# Druga_p_ytka.net
KiCad netlist of a schematic drawn in EAGLE
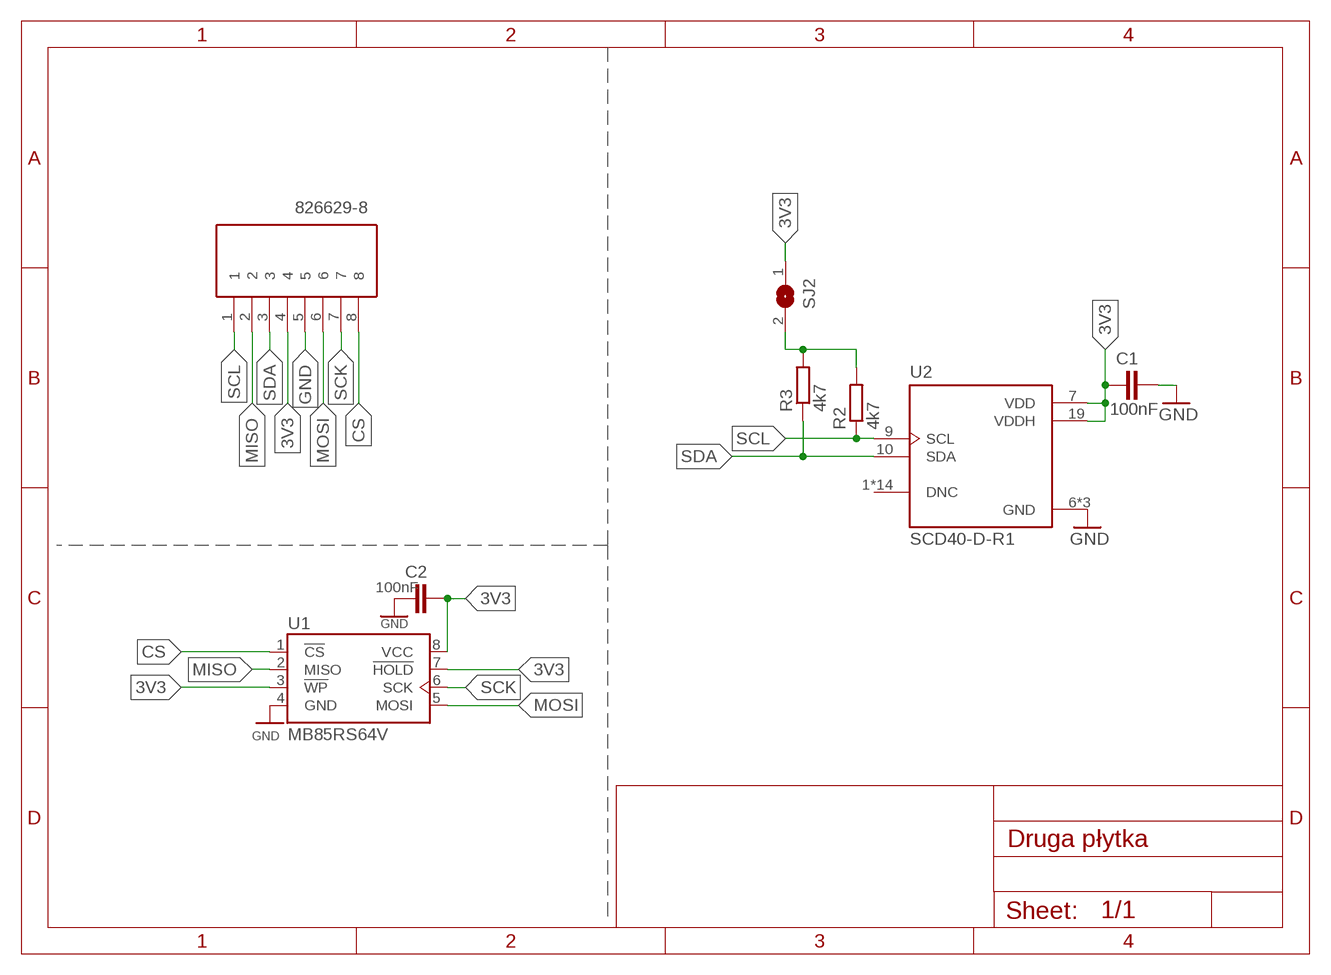
[diagram p0: schematic, sheet 1]

(export (version "E")
  (design (tool "Eeschema 10.0.6"))
  (components
    (comp (ref "C1")
      (value "100nF")
      (footprint "eagle-import:C0402")
      (libsource (lib "eagle-import") (part "C-EUC0402"))
    )
    (comp (ref "C2")
      (value "100nF")
      (footprint "eagle-import:C0402")
      (libsource (lib "eagle-import") (part "C-EUC0402"))
    )
    (comp (ref "J1")
      (value "826629-8")
      (footprint "eagle-import:HDRV8W63P0X254_1X8_2032X250X95")
      (fields (field (name "MOUSER_PART_NUMBER") "571-826629-8"))
      (libsource (lib "eagle-import") (part "826629-8"))
    )
    (comp (ref "R2")
      (value "4k7")
      (footprint "eagle-import:R1206")
      (libsource (lib "eagle-import") (part "R-EU_R1206"))
    )
    (comp (ref "R3")
      (value "4k7")
      (footprint "eagle-import:R1206")
      (libsource (lib "eagle-import") (part "R-EU_R1206"))
    )
    (comp (ref "SJ2") (value "SJ") (footprint "eagle-import:SJ") (libsource (lib "eagle-import") (part "SJ")))
    (comp (ref "U1")
      (value "MB85RS64V")
      (footprint "eagle-import:SOIC127P600X155-8_R159_68_374R15")
      (fields (field (name "MF") "Fujitsu"))
      (libsource (lib "eagle-import") (part "MB85RS64V"))
    )
    (comp (ref "U2")
      (value "SCD40-D-R1")
      (footprint "eagle-import:XDCR_SCD40-D-R1")
      (fields (field (name "MF") "Sensirion AG"))
      (libsource (lib "eagle-import") (part "SCD40-D-R1"))
    )
  )
  (nets
    (net (code "1") (name "3V3") (class "Default")
      (node (ref "C1") (pin "2") (pinfunction "2_2") (pintype "passive"))
      (node (ref "C2") (pin "1") (pinfunction "1_1") (pintype "passive"))
      (node (ref "J1") (pin "4") (pinfunction "4_4") (pintype "bidirectional"))
      (node (ref "SJ2") (pin "1") (pinfunction "1_1") (pintype "passive"))
      (node (ref "U1") (pin "3") (pinfunction "~{WP}_3") (pintype "input"))
      (node (ref "U1") (pin "7") (pinfunction "~{HOLD}_7") (pintype "input"))
      (node (ref "U1") (pin "8") (pinfunction "VCC_8") (pintype "power_in"))
      (node (ref "U2") (pin "19") (pinfunction "VDDH_19") (pintype "power_in"))
      (node (ref "U2") (pin "7") (pinfunction "VDD_7") (pintype "power_in"))
    )
    (net (code "2") (name "CS") (class "Default")
      (node (ref "J1") (pin "8") (pinfunction "8_8") (pintype "bidirectional"))
      (node (ref "U1") (pin "1") (pinfunction "~{CS}_1") (pintype "input"))
    )
    (net (code "3") (name "GND") (class "Default")
      (node (ref "C1") (pin "1") (pinfunction "1_1") (pintype "passive"))
      (node (ref "C2") (pin "2") (pinfunction "2_2") (pintype "passive"))
      (node (ref "J1") (pin "5") (pinfunction "5_5") (pintype "bidirectional"))
      (node (ref "U1") (pin "4") (pinfunction "GND_4") (pintype "power_in"))
      (node (ref "U2") (pin "20") (pinfunction "GND_20") (pintype "power_in"))
      (node (ref "U2") (pin "21") (pinfunction "GND_21") (pintype "power_in"))
      (node (ref "U2") (pin "6") (pinfunction "GND_6") (pintype "power_in"))
    )
    (net (code "4") (name "MISO") (class "Default")
      (node (ref "J1") (pin "2") (pinfunction "2_2") (pintype "bidirectional"))
      (node (ref "U1") (pin "2") (pinfunction "MISO_2") (pintype "output"))
    )
    (net (code "5") (name "MOSI") (class "Default")
      (node (ref "J1") (pin "6") (pinfunction "6_6") (pintype "bidirectional"))
      (node (ref "U1") (pin "5") (pinfunction "MOSI_5") (pintype "input"))
    )
    (net (code "6") (name "Net-(R2-Pad2)") (class "Default")
      (node (ref "R2") (pin "2") (pinfunction "2_2") (pintype "passive"))
      (node (ref "R3") (pin "2") (pinfunction "2_2") (pintype "passive"))
      (node (ref "SJ2") (pin "2") (pinfunction "2_2") (pintype "passive"))
    )
    (net (code "7") (name "SCK") (class "Default")
      (node (ref "J1") (pin "7") (pinfunction "7_7") (pintype "bidirectional"))
      (node (ref "U1") (pin "6") (pinfunction "SCK_6") (pintype "input"))
    )
    (net (code "8") (name "SCL") (class "Default")
      (node (ref "J1") (pin "1") (pinfunction "1_1") (pintype "bidirectional"))
      (node (ref "R2") (pin "1") (pinfunction "1_1") (pintype "passive"))
      (node (ref "U2") (pin "9") (pinfunction "SCL_9") (pintype "input"))
    )
    (net (code "9") (name "SDA") (class "Default")
      (node (ref "J1") (pin "3") (pinfunction "3_3") (pintype "bidirectional"))
      (node (ref "R3") (pin "1") (pinfunction "1_1") (pintype "passive"))
      (node (ref "U2") (pin "10") (pinfunction "SDA_10") (pintype "bidirectional"))
    )
    (net (code "10") (name "unconnected-(U2-DNC-Pad1)") (class "Default")
      (node (ref "U2") (pin "1") (pinfunction "DNC_1") (pintype "no_connect"))
    )
    (net (code "11") (name "unconnected-(U2-DNC-Pad2)") (class "Default")
      (node (ref "U2") (pin "2") (pinfunction "DNC_2") (pintype "no_connect"))
    )
    (net (code "12") (name "unconnected-(U2-DNC-Pad3)") (class "Default")
      (node (ref "U2") (pin "3") (pinfunction "DNC_3") (pintype "no_connect"))
    )
    (net (code "13") (name "unconnected-(U2-DNC-Pad4)") (class "Default")
      (node (ref "U2") (pin "4") (pinfunction "DNC_4") (pintype "no_connect"))
    )
    (net (code "14") (name "unconnected-(U2-DNC-Pad5)") (class "Default")
      (node (ref "U2") (pin "5") (pinfunction "DNC_5") (pintype "no_connect"))
    )
    (net (code "15") (name "unconnected-(U2-DNC-Pad8)") (class "Default")
      (node (ref "U2") (pin "8") (pinfunction "DNC_8") (pintype "no_connect"))
    )
    (net (code "16") (name "unconnected-(U2-DNC-Pad11)") (class "Default")
      (node (ref "U2") (pin "11") (pinfunction "DNC_11") (pintype "no_connect"))
    )
    (net (code "17") (name "unconnected-(U2-DNC-Pad12)") (class "Default")
      (node (ref "U2") (pin "12") (pinfunction "DNC_12") (pintype "no_connect"))
    )
    (net (code "18") (name "unconnected-(U2-DNC-Pad13)") (class "Default")
      (node (ref "U2") (pin "13") (pinfunction "DNC_13") (pintype "no_connect"))
    )
    (net (code "19") (name "unconnected-(U2-DNC-Pad14)") (class "Default")
      (node (ref "U2") (pin "14") (pinfunction "DNC_14") (pintype "no_connect"))
    )
    (net (code "20") (name "unconnected-(U2-DNC-Pad15)") (class "Default")
      (node (ref "U2") (pin "15") (pinfunction "DNC_15") (pintype "no_connect"))
    )
    (net (code "21") (name "unconnected-(U2-DNC-Pad16)") (class "Default")
      (node (ref "U2") (pin "16") (pinfunction "DNC_16") (pintype "no_connect"))
    )
    (net (code "22") (name "unconnected-(U2-DNC-Pad17)") (class "Default")
      (node (ref "U2") (pin "17") (pinfunction "DNC_17") (pintype "no_connect"))
    )
    (net (code "23") (name "unconnected-(U2-DNC-Pad18)") (class "Default")
      (node (ref "U2") (pin "18") (pinfunction "DNC_18") (pintype "no_connect"))
    )
  )
)
